# AD5541.net
KiCad netlist of a schematic drawn in Altium Designer
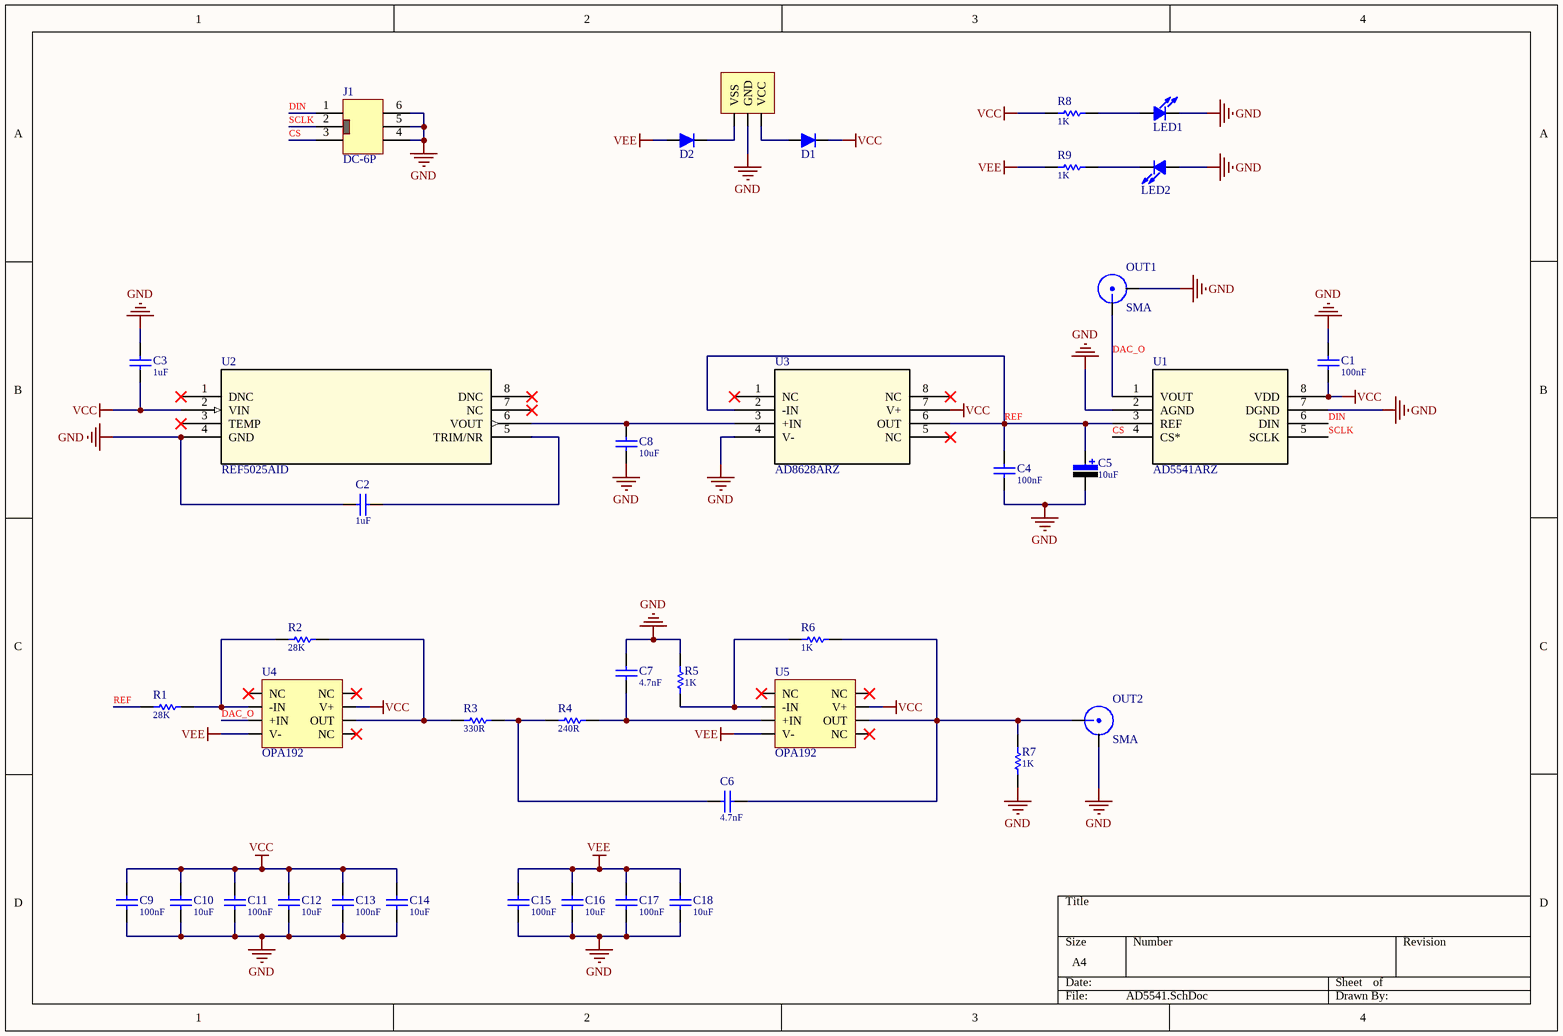
[diagram p0: AD5541.SchDoc]

(export (version "E")
  (design (tool "Eeschema 10.0.6"))
  (components
    (comp (ref "C1")
      (value "100nF")
      (footprint "C0603-L")
      (description "贴片瓷片电容")
      (fields (field (name "Comment") "Cap-S"))
      (libsource (lib "XuZhe") (part "Cap-S"))
    )
    (comp (ref "C2")
      (value "1uF")
      (footprint "C0603-L")
      (description "贴片瓷片电容")
      (fields (field (name "Comment") "Cap-S"))
      (libsource (lib "XuZhe") (part "Cap-S"))
    )
    (comp (ref "C3")
      (value "1uF")
      (footprint "C0603-L")
      (description "贴片瓷片电容")
      (fields (field (name "Comment") "Cap-S"))
      (libsource (lib "XuZhe") (part "Cap-S"))
    )
    (comp (ref "C4")
      (value "100nF")
      (footprint "C0603-L")
      (description "贴片瓷片电容")
      (fields (field (name "Comment") "Cap-S"))
      (libsource (lib "XuZhe") (part "Cap-S"))
    )
    (comp (ref "C5")
      (value "10uF")
      (footprint "C-DIP-8")
      (description "极性直插电解电容")
      (fields (field (name "Comment") "C"))
      (libsource (lib "XuZhe") (part "Cap-Pol-ER"))
    )
    (comp (ref "C6")
      (value "4.7nF")
      (footprint "C0603-L")
      (description "贴片瓷片电容")
      (fields (field (name "Comment") "Cap-S"))
      (libsource (lib "XuZhe") (part "Cap-S"))
    )
    (comp (ref "C7")
      (value "4.7nF")
      (footprint "C0603-L")
      (description "贴片瓷片电容")
      (fields (field (name "Comment") "Cap-S"))
      (libsource (lib "XuZhe") (part "Cap-S"))
    )
    (comp (ref "C8")
      (value "10uF")
      (footprint "C0603-L")
      (description "贴片瓷片电容")
      (fields (field (name "Comment") "Cap-S"))
      (libsource (lib "XuZhe") (part "Cap-S"))
    )
    (comp (ref "C9")
      (value "100nF")
      (footprint "C0603-L")
      (description "贴片瓷片电容")
      (fields (field (name "Comment") "Cap-S"))
      (libsource (lib "XuZhe") (part "Cap-S"))
    )
    (comp (ref "C10")
      (value "10uF")
      (footprint "C0603-L")
      (description "贴片瓷片电容")
      (fields (field (name "Comment") "Cap-S"))
      (libsource (lib "XuZhe") (part "Cap-S"))
    )
    (comp (ref "C11")
      (value "100nF")
      (footprint "C0603-L")
      (description "贴片瓷片电容")
      (fields (field (name "Comment") "Cap-S"))
      (libsource (lib "XuZhe") (part "Cap-S"))
    )
    (comp (ref "C12")
      (value "10uF")
      (footprint "C0603-L")
      (description "贴片瓷片电容")
      (fields (field (name "Comment") "Cap-S"))
      (libsource (lib "XuZhe") (part "Cap-S"))
    )
    (comp (ref "C13")
      (value "100nF")
      (footprint "C0603-L")
      (description "贴片瓷片电容")
      (fields (field (name "Comment") "Cap-S"))
      (libsource (lib "XuZhe") (part "Cap-S"))
    )
    (comp (ref "C14")
      (value "10uF")
      (footprint "C0603-L")
      (description "贴片瓷片电容")
      (fields (field (name "Comment") "Cap-S"))
      (libsource (lib "XuZhe") (part "Cap-S"))
    )
    (comp (ref "C15")
      (value "100nF")
      (footprint "C0603-L")
      (description "贴片瓷片电容")
      (fields (field (name "Comment") "Cap-S"))
      (libsource (lib "XuZhe") (part "Cap-S"))
    )
    (comp (ref "C16")
      (value "10uF")
      (footprint "C0603-L")
      (description "贴片瓷片电容")
      (fields (field (name "Comment") "Cap-S"))
      (libsource (lib "XuZhe") (part "Cap-S"))
    )
    (comp (ref "C17")
      (value "100nF")
      (footprint "C0603-L")
      (description "贴片瓷片电容")
      (fields (field (name "Comment") "Cap-S"))
      (libsource (lib "XuZhe") (part "Cap-S"))
    )
    (comp (ref "C18")
      (value "10uF")
      (footprint "C0603-L")
      (description "贴片瓷片电容")
      (fields (field (name "Comment") "Cap-S"))
      (libsource (lib "XuZhe") (part "Cap-S"))
    )
    (comp (ref "D1")
      (value "D")
      (footprint "D-SMA")
      (description "二极管")
      (libsource (lib "XuZhe") (part "Diode"))
    )
    (comp (ref "D2")
      (value "D")
      (footprint "D-SMA")
      (description "二极管")
      (libsource (lib "XuZhe") (part "Diode"))
    )
    (comp (ref "J1") (value "DC-6P") (footprint "DC-6P") (libsource (lib "XuZhe") (part "DC-6P")))
    (comp (ref "J2")
      (value "Power-3P")
      (footprint "SIPA03")
      (description "供电端子")
      (libsource (lib "XuZhe") (part "Power-3P"))
    )
    (comp (ref "LED1")
      (value "LED")
      (footprint "Led-0805_L")
      (description "发光二极管")
      (libsource (lib "XuZhe") (part "LED"))
    )
    (comp (ref "LED2")
      (value "LED")
      (footprint "Led-0805_L")
      (description "发光二极管")
      (libsource (lib "XuZhe") (part "LED"))
    )
    (comp (ref "OUT1") (value "SMA") (footprint "SMA1") (libsource (lib "XuZhe") (part "SMA")))
    (comp (ref "OUT2") (value "SMA") (footprint "SMA1") (libsource (lib "XuZhe") (part "SMA")))
    (comp (ref "R1")
      (value "28K")
      (footprint "R0603-L")
      (description "贴片电阻")
      (fields (field (name "Comment") "R"))
      (libsource (lib "XuZhe") (part "Res"))
    )
    (comp (ref "R2")
      (value "28K")
      (footprint "R0603-L")
      (description "贴片电阻")
      (fields (field (name "Comment") "R"))
      (libsource (lib "XuZhe") (part "Res"))
    )
    (comp (ref "R3")
      (value "330R")
      (footprint "R0603-L")
      (description "贴片电阻")
      (fields (field (name "Comment") "R"))
      (libsource (lib "XuZhe") (part "Res"))
    )
    (comp (ref "R4")
      (value "240R")
      (footprint "R0603-L")
      (description "贴片电阻")
      (fields (field (name "Comment") "R"))
      (libsource (lib "XuZhe") (part "Res"))
    )
    (comp (ref "R5")
      (value "1K")
      (footprint "R0603-L")
      (description "贴片电阻")
      (fields (field (name "Comment") "R"))
      (libsource (lib "XuZhe") (part "Res"))
    )
    (comp (ref "R6")
      (value "1K")
      (footprint "R0603-L")
      (description "贴片电阻")
      (fields (field (name "Comment") "R"))
      (libsource (lib "XuZhe") (part "Res"))
    )
    (comp (ref "R7")
      (value "1K")
      (footprint "R0603-L")
      (description "贴片电阻")
      (fields (field (name "Comment") "R"))
      (libsource (lib "XuZhe") (part "Res"))
    )
    (comp (ref "R8")
      (value "1K")
      (footprint "R0603-L")
      (description "贴片电阻")
      (fields (field (name "Comment") "R"))
      (libsource (lib "XuZhe") (part "Res"))
    )
    (comp (ref "R9")
      (value "1K")
      (footprint "R0603-L")
      (description "贴片电阻")
      (fields (field (name "Comment") "R"))
      (libsource (lib "XuZhe") (part "Res"))
    )
    (comp (ref "U1")
      (value "AD5541ARZ")
      (footprint "R_8_ADI")
      (description "No Description Available")
      (fields (field (name "COPYRIGHT") "Copyright (C) 2021 Ultra Librarian. All rights reserved."))
      (libsource (lib "AD5541ARZ") (part "AD5541ARZ"))
    )
    (comp (ref "U2")
      (value "REF5025AID")
      (footprint "D8")
      (description "No Description Available")
      (fields (field (name "COPYRIGHT") "Copyright (C) 2021 Ultra Librarian. All rights reserved."))
      (libsource (lib "REF5025AID") (part "REF5025AID"))
    )
    (comp (ref "U3")
      (value "AD8628ARZ")
      (footprint "R_8_ADI")
      (description "No Description Available")
      (fields (field (name "COPYRIGHT") "Copyright (C) 2021 Ultra Librarian. All rights reserved."))
      (libsource (lib "AD8628ARZ") (part "AD8628ARZ"))
    )
    (comp (ref "U4")
      (value "OPA192")
      (footprint "SOIC127P600X175-8N")
      (libsource (lib "OPA192") (part "OPA192"))
    )
    (comp (ref "U5")
      (value "OPA192")
      (footprint "SOIC127P600X175-8N")
      (libsource (lib "OPA192") (part "OPA192"))
    )
  )
  (nets
    (net (code "1") (name "/CS") (class "Default")
      (node (ref "J1") (pin "3") (pinfunction "3_3") (pintype "passive"))
      (node (ref "U1") (pin "4") (pinfunction "CS*_4") (pintype "passive"))
    )
    (net (code "2") (name "/DAC_O") (class "Default")
      (node (ref "OUT1") (pin "1") (pinfunction "1_1") (pintype "passive"))
      (node (ref "U1") (pin "1") (pinfunction "VOUT_1") (pintype "passive"))
      (node (ref "U4") (pin "3") (pinfunction "+IN_3") (pintype "passive"))
    )
    (net (code "3") (name "/DIN") (class "Default")
      (node (ref "J1") (pin "1") (pinfunction "1_1") (pintype "passive"))
      (node (ref "U1") (pin "6") (pinfunction "DIN_6") (pintype "passive"))
    )
    (net (code "4") (name "/REF") (class "Default")
      (node (ref "C4") (pin "2") (pinfunction "2_2") (pintype "passive"))
      (node (ref "C5") (pin "1") (pinfunction "1_1") (pintype "passive"))
      (node (ref "R1") (pin "1") (pinfunction "1_1") (pintype "passive"))
      (node (ref "U1") (pin "3") (pinfunction "REF_3") (pintype "passive"))
      (node (ref "U3") (pin "2") (pinfunction "-IN_2") (pintype "passive"))
      (node (ref "U3") (pin "6") (pinfunction "OUT_6") (pintype "passive"))
    )
    (net (code "5") (name "/SCLK") (class "Default")
      (node (ref "J1") (pin "2") (pinfunction "2_2") (pintype "passive"))
      (node (ref "U1") (pin "5") (pinfunction "SCLK_5") (pintype "passive"))
    )
    (net (code "6") (name "GND") (class "Default")
      (node (ref "C1") (pin "2") (pinfunction "2_2") (pintype "passive"))
      (node (ref "C10") (pin "1") (pinfunction "1_1") (pintype "passive"))
      (node (ref "C11") (pin "1") (pinfunction "1_1") (pintype "passive"))
      (node (ref "C12") (pin "1") (pinfunction "1_1") (pintype "passive"))
      (node (ref "C13") (pin "1") (pinfunction "1_1") (pintype "passive"))
      (node (ref "C14") (pin "1") (pinfunction "1_1") (pintype "passive"))
      (node (ref "C15") (pin "1") (pinfunction "1_1") (pintype "passive"))
      (node (ref "C16") (pin "1") (pinfunction "1_1") (pintype "passive"))
      (node (ref "C17") (pin "1") (pinfunction "1_1") (pintype "passive"))
      (node (ref "C18") (pin "1") (pinfunction "1_1") (pintype "passive"))
      (node (ref "C2") (pin "1") (pinfunction "1_1") (pintype "passive"))
      (node (ref "C3") (pin "2") (pinfunction "2_2") (pintype "passive"))
      (node (ref "C4") (pin "1") (pinfunction "1_1") (pintype "passive"))
      (node (ref "C5") (pin "2") (pinfunction "2_2") (pintype "passive"))
      (node (ref "C7") (pin "2") (pinfunction "2_2") (pintype "passive"))
      (node (ref "C8") (pin "1") (pinfunction "1_1") (pintype "passive"))
      (node (ref "C9") (pin "1") (pinfunction "1_1") (pintype "passive"))
      (node (ref "J1") (pin "4") (pinfunction "4_4") (pintype "passive"))
      (node (ref "J1") (pin "5") (pinfunction "5_5") (pintype "passive"))
      (node (ref "J1") (pin "6") (pinfunction "6_6") (pintype "passive"))
      (node (ref "J2") (pin "2") (pinfunction "GND_2") (pintype "passive"))
      (node (ref "LED1") (pin "2") (pinfunction "2_2") (pintype "passive"))
      (node (ref "LED2") (pin "1") (pinfunction "1_1") (pintype "passive"))
      (node (ref "OUT1") (pin "2") (pinfunction "2_2") (pintype "passive"))
      (node (ref "OUT2") (pin "2") (pinfunction "2_2") (pintype "passive"))
      (node (ref "R5") (pin "1") (pinfunction "1_1") (pintype "passive"))
      (node (ref "R7") (pin "1") (pinfunction "1_1") (pintype "passive"))
      (node (ref "U1") (pin "2") (pinfunction "AGND_2") (pintype "passive"))
      (node (ref "U1") (pin "7") (pinfunction "DGND_7") (pintype "passive"))
      (node (ref "U2") (pin "4") (pinfunction "GND_4") (pintype "passive"))
      (node (ref "U3") (pin "4") (pinfunction "V-_4") (pintype "power_in"))
    )
    (net (code "7") (name "Net-(C6-Pad1)") (class "Default")
      (node (ref "C6") (pin "1") (pinfunction "1_1") (pintype "passive"))
      (node (ref "R3") (pin "2") (pinfunction "2_2") (pintype "passive"))
      (node (ref "R4") (pin "1") (pinfunction "1_1") (pintype "passive"))
    )
    (net (code "8") (name "Net-(J2-VCC)") (class "Default")
      (node (ref "D1") (pin "1") (pinfunction "1_1") (pintype "passive"))
      (node (ref "J2") (pin "1") (pinfunction "VCC_1") (pintype "passive"))
    )
    (net (code "9") (name "Net-(J2-VSS)") (class "Default")
      (node (ref "D2") (pin "2") (pinfunction "2_2") (pintype "passive"))
      (node (ref "J2") (pin "3") (pinfunction "VSS_3") (pintype "passive"))
    )
    (net (code "10") (name "Net-(LED1-Pad1)") (class "Default")
      (node (ref "LED1") (pin "1") (pinfunction "1_1") (pintype "passive"))
      (node (ref "R8") (pin "2") (pinfunction "2_2") (pintype "passive"))
    )
    (net (code "11") (name "Net-(LED2-Pad2)") (class "Default")
      (node (ref "LED2") (pin "2") (pinfunction "2_2") (pintype "passive"))
      (node (ref "R9") (pin "2") (pinfunction "2_2") (pintype "passive"))
    )
    (net (code "12") (name "Net-(U2-TRIM{slash}NR)") (class "Default")
      (node (ref "C2") (pin "2") (pinfunction "2_2") (pintype "passive"))
      (node (ref "U2") (pin "5") (pinfunction "TRIM/NR_5") (pintype "passive"))
    )
    (net (code "13") (name "Net-(U2-VOUT)") (class "Default")
      (node (ref "C8") (pin "2") (pinfunction "2_2") (pintype "passive"))
      (node (ref "U2") (pin "6") (pinfunction "VOUT_6") (pintype "output"))
      (node (ref "U3") (pin "3") (pinfunction "+IN_3") (pintype "passive"))
    )
    (net (code "14") (name "Net-(U4--IN)") (class "Default")
      (node (ref "R1") (pin "2") (pinfunction "2_2") (pintype "passive"))
      (node (ref "R2") (pin "1") (pinfunction "1_1") (pintype "passive"))
      (node (ref "U4") (pin "2") (pinfunction "-IN_2") (pintype "passive"))
    )
    (net (code "15") (name "Net-(U4-OUT)") (class "Default")
      (node (ref "R2") (pin "2") (pinfunction "2_2") (pintype "passive"))
      (node (ref "R3") (pin "1") (pinfunction "1_1") (pintype "passive"))
      (node (ref "U4") (pin "6") (pinfunction "OUT_6") (pintype "passive"))
    )
    (net (code "16") (name "Net-(U5-+IN)") (class "Default")
      (node (ref "C7") (pin "1") (pinfunction "1_1") (pintype "passive"))
      (node (ref "R4") (pin "2") (pinfunction "2_2") (pintype "passive"))
      (node (ref "U5") (pin "3") (pinfunction "+IN_3") (pintype "passive"))
    )
    (net (code "17") (name "Net-(U5--IN)") (class "Default")
      (node (ref "R5") (pin "2") (pinfunction "2_2") (pintype "passive"))
      (node (ref "R6") (pin "1") (pinfunction "1_1") (pintype "passive"))
      (node (ref "U5") (pin "2") (pinfunction "-IN_2") (pintype "passive"))
    )
    (net (code "18") (name "Net-(U5-OUT)") (class "Default")
      (node (ref "C6") (pin "2") (pinfunction "2_2") (pintype "passive"))
      (node (ref "OUT2") (pin "1") (pinfunction "1_1") (pintype "passive"))
      (node (ref "R6") (pin "2") (pinfunction "2_2") (pintype "passive"))
      (node (ref "R7") (pin "2") (pinfunction "2_2") (pintype "passive"))
      (node (ref "U5") (pin "6") (pinfunction "OUT_6") (pintype "passive"))
    )
    (net (code "19") (name "VCC") (class "Default")
      (node (ref "C1") (pin "1") (pinfunction "1_1") (pintype "passive"))
      (node (ref "C10") (pin "2") (pinfunction "2_2") (pintype "passive"))
      (node (ref "C11") (pin "2") (pinfunction "2_2") (pintype "passive"))
      (node (ref "C12") (pin "2") (pinfunction "2_2") (pintype "passive"))
      (node (ref "C13") (pin "2") (pinfunction "2_2") (pintype "passive"))
      (node (ref "C14") (pin "2") (pinfunction "2_2") (pintype "passive"))
      (node (ref "C3") (pin "1") (pinfunction "1_1") (pintype "passive"))
      (node (ref "C9") (pin "2") (pinfunction "2_2") (pintype "passive"))
      (node (ref "D1") (pin "2") (pinfunction "2_2") (pintype "passive"))
      (node (ref "R8") (pin "1") (pinfunction "1_1") (pintype "passive"))
      (node (ref "U1") (pin "8") (pinfunction "VDD_8") (pintype "power_in"))
      (node (ref "U2") (pin "2") (pinfunction "VIN_2") (pintype "input"))
      (node (ref "U3") (pin "7") (pinfunction "V+_7") (pintype "power_in"))
      (node (ref "U4") (pin "7") (pinfunction "V+_7") (pintype "passive"))
      (node (ref "U5") (pin "7") (pinfunction "V+_7") (pintype "passive"))
    )
    (net (code "20") (name "VEE") (class "Default")
      (node (ref "C15") (pin "2") (pinfunction "2_2") (pintype "passive"))
      (node (ref "C16") (pin "2") (pinfunction "2_2") (pintype "passive"))
      (node (ref "C17") (pin "2") (pinfunction "2_2") (pintype "passive"))
      (node (ref "C18") (pin "2") (pinfunction "2_2") (pintype "passive"))
      (node (ref "D2") (pin "1") (pinfunction "1_1") (pintype "passive"))
      (node (ref "R9") (pin "1") (pinfunction "1_1") (pintype "passive"))
      (node (ref "U4") (pin "4") (pinfunction "V-_4") (pintype "passive"))
      (node (ref "U5") (pin "4") (pinfunction "V-_4") (pintype "passive"))
    )
    (net (code "21") (name "unconnected-(U2-DNC-Pad1)") (class "Default")
      (node (ref "U2") (pin "1") (pinfunction "DNC_1") (pintype "passive+no_connect"))
    )
    (net (code "22") (name "unconnected-(U2-DNC-Pad8)") (class "Default")
      (node (ref "U2") (pin "8") (pinfunction "DNC_8") (pintype "passive+no_connect"))
    )
    (net (code "23") (name "unconnected-(U2-NC-Pad7)") (class "Default")
      (node (ref "U2") (pin "7") (pinfunction "NC_7") (pintype "passive+no_connect"))
    )
    (net (code "24") (name "unconnected-(U2-TEMP-Pad3)") (class "Default")
      (node (ref "U2") (pin "3") (pinfunction "TEMP_3") (pintype "passive+no_connect"))
    )
    (net (code "25") (name "unconnected-(U3-NC-Pad1)") (class "Default")
      (node (ref "U3") (pin "1") (pinfunction "NC_1") (pintype "passive+no_connect"))
    )
    (net (code "26") (name "unconnected-(U3-NC-Pad5)") (class "Default")
      (node (ref "U3") (pin "5") (pinfunction "NC_5") (pintype "passive+no_connect"))
    )
    (net (code "27") (name "unconnected-(U3-NC-Pad8)") (class "Default")
      (node (ref "U3") (pin "8") (pinfunction "NC_8") (pintype "passive+no_connect"))
    )
    (net (code "28") (name "unconnected-(U4-NC-Pad1)") (class "Default")
      (node (ref "U4") (pin "1") (pinfunction "NC_1") (pintype "passive+no_connect"))
    )
    (net (code "29") (name "unconnected-(U4-NC-Pad5)") (class "Default")
      (node (ref "U4") (pin "5") (pinfunction "NC_5") (pintype "passive+no_connect"))
    )
    (net (code "30") (name "unconnected-(U4-NC-Pad8)") (class "Default")
      (node (ref "U4") (pin "8") (pinfunction "NC_8") (pintype "passive+no_connect"))
    )
    (net (code "31") (name "unconnected-(U5-NC-Pad1)") (class "Default")
      (node (ref "U5") (pin "1") (pinfunction "NC_1") (pintype "passive+no_connect"))
    )
    (net (code "32") (name "unconnected-(U5-NC-Pad5)") (class "Default")
      (node (ref "U5") (pin "5") (pinfunction "NC_5") (pintype "passive+no_connect"))
    )
    (net (code "33") (name "unconnected-(U5-NC-Pad8)") (class "Default")
      (node (ref "U5") (pin "8") (pinfunction "NC_8") (pintype "passive+no_connect"))
    )
  )
)
